# BPMLabRXDriver.net
KiCad netlist of a schematic drawn in EAGLE
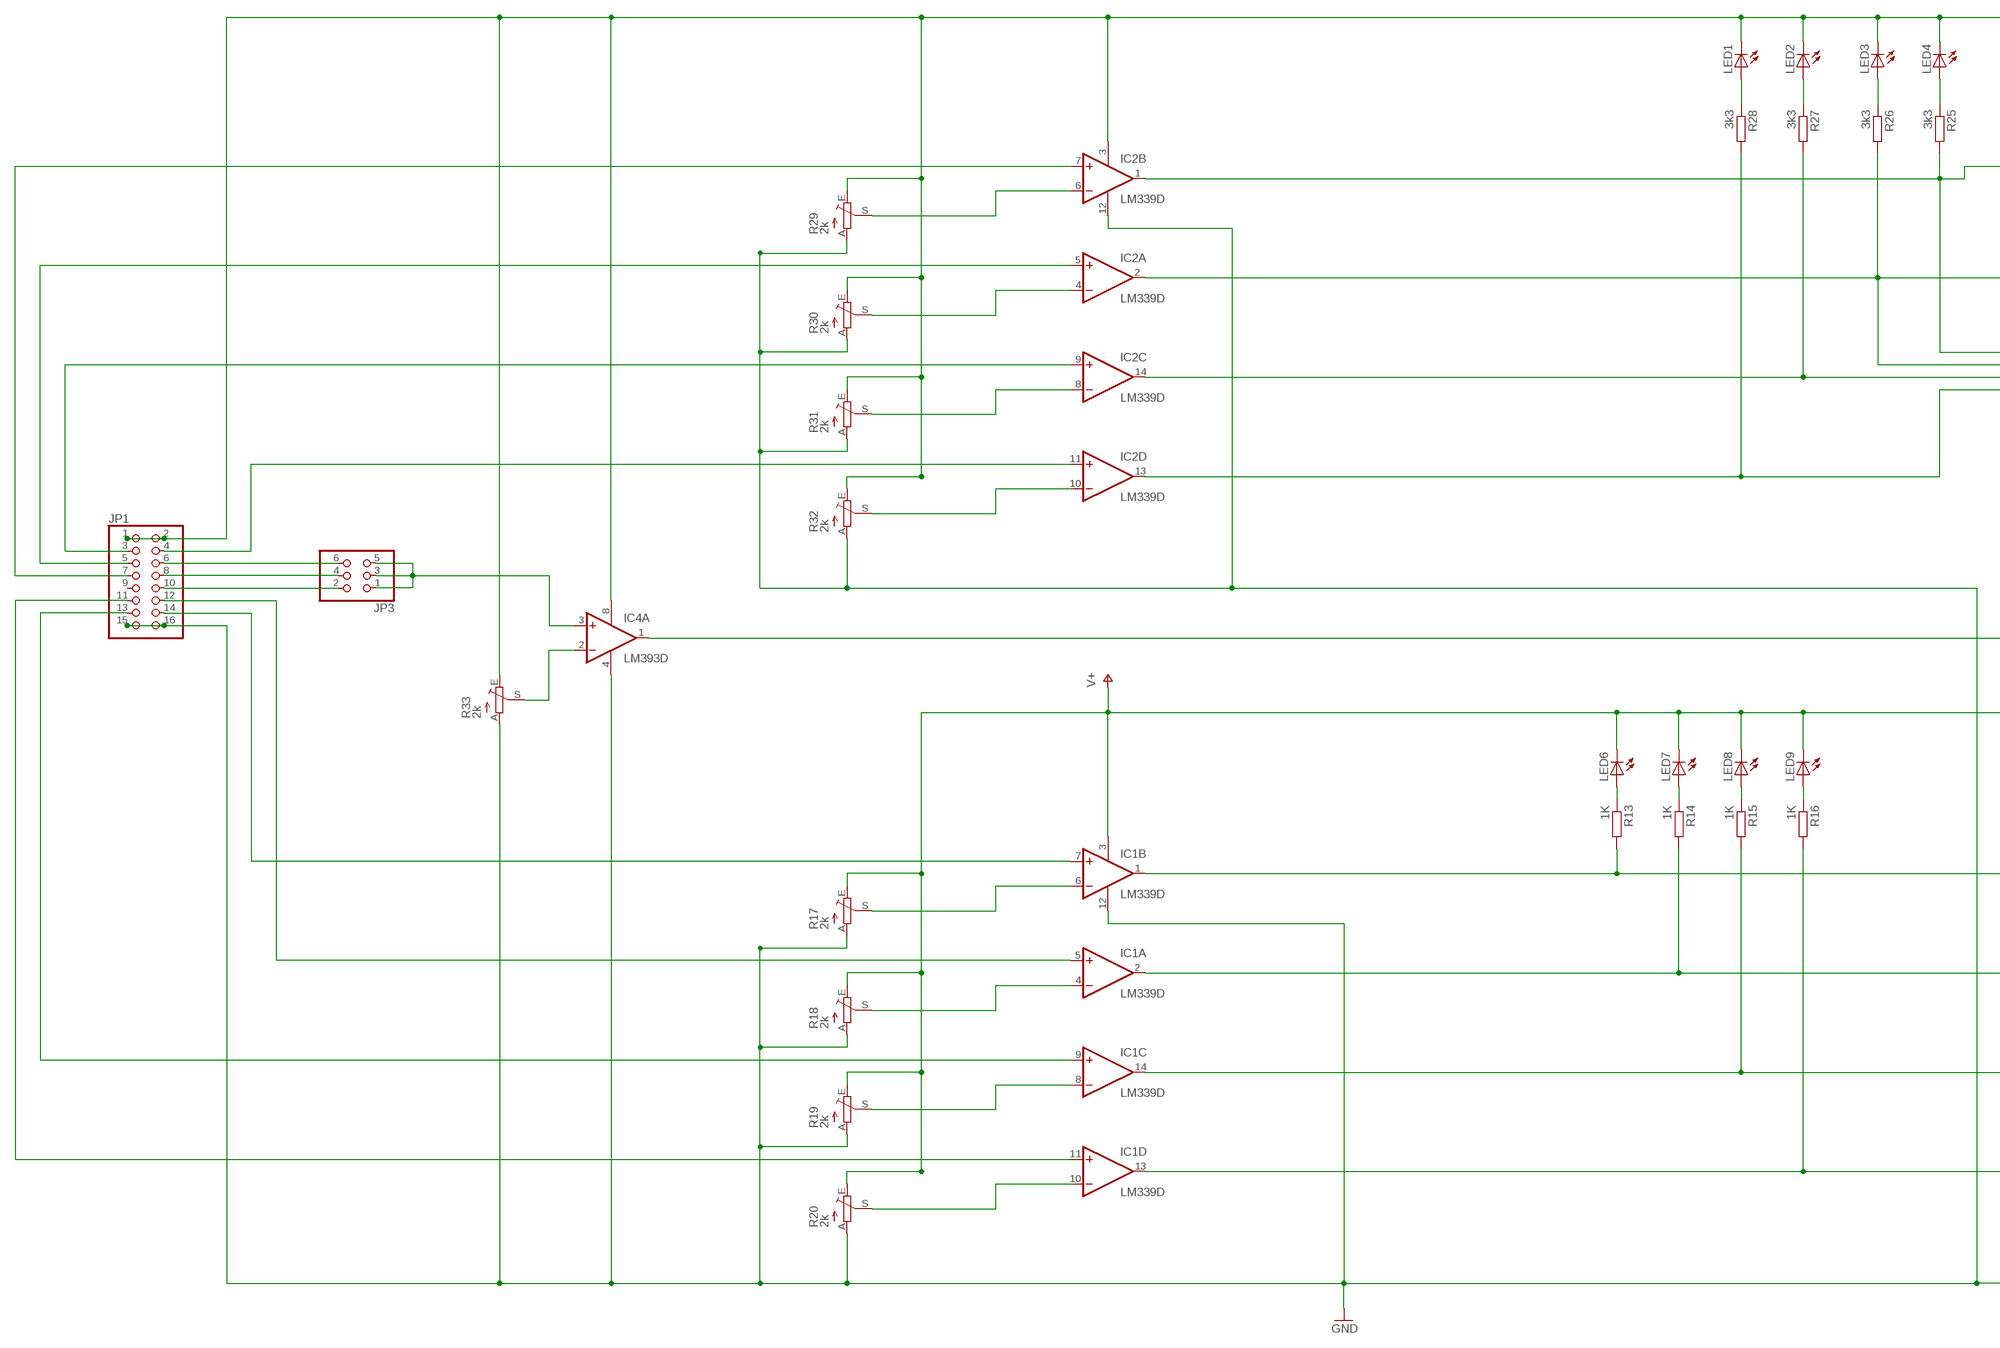
[diagram p0: schematic, sheet 1, part 1 of 2]
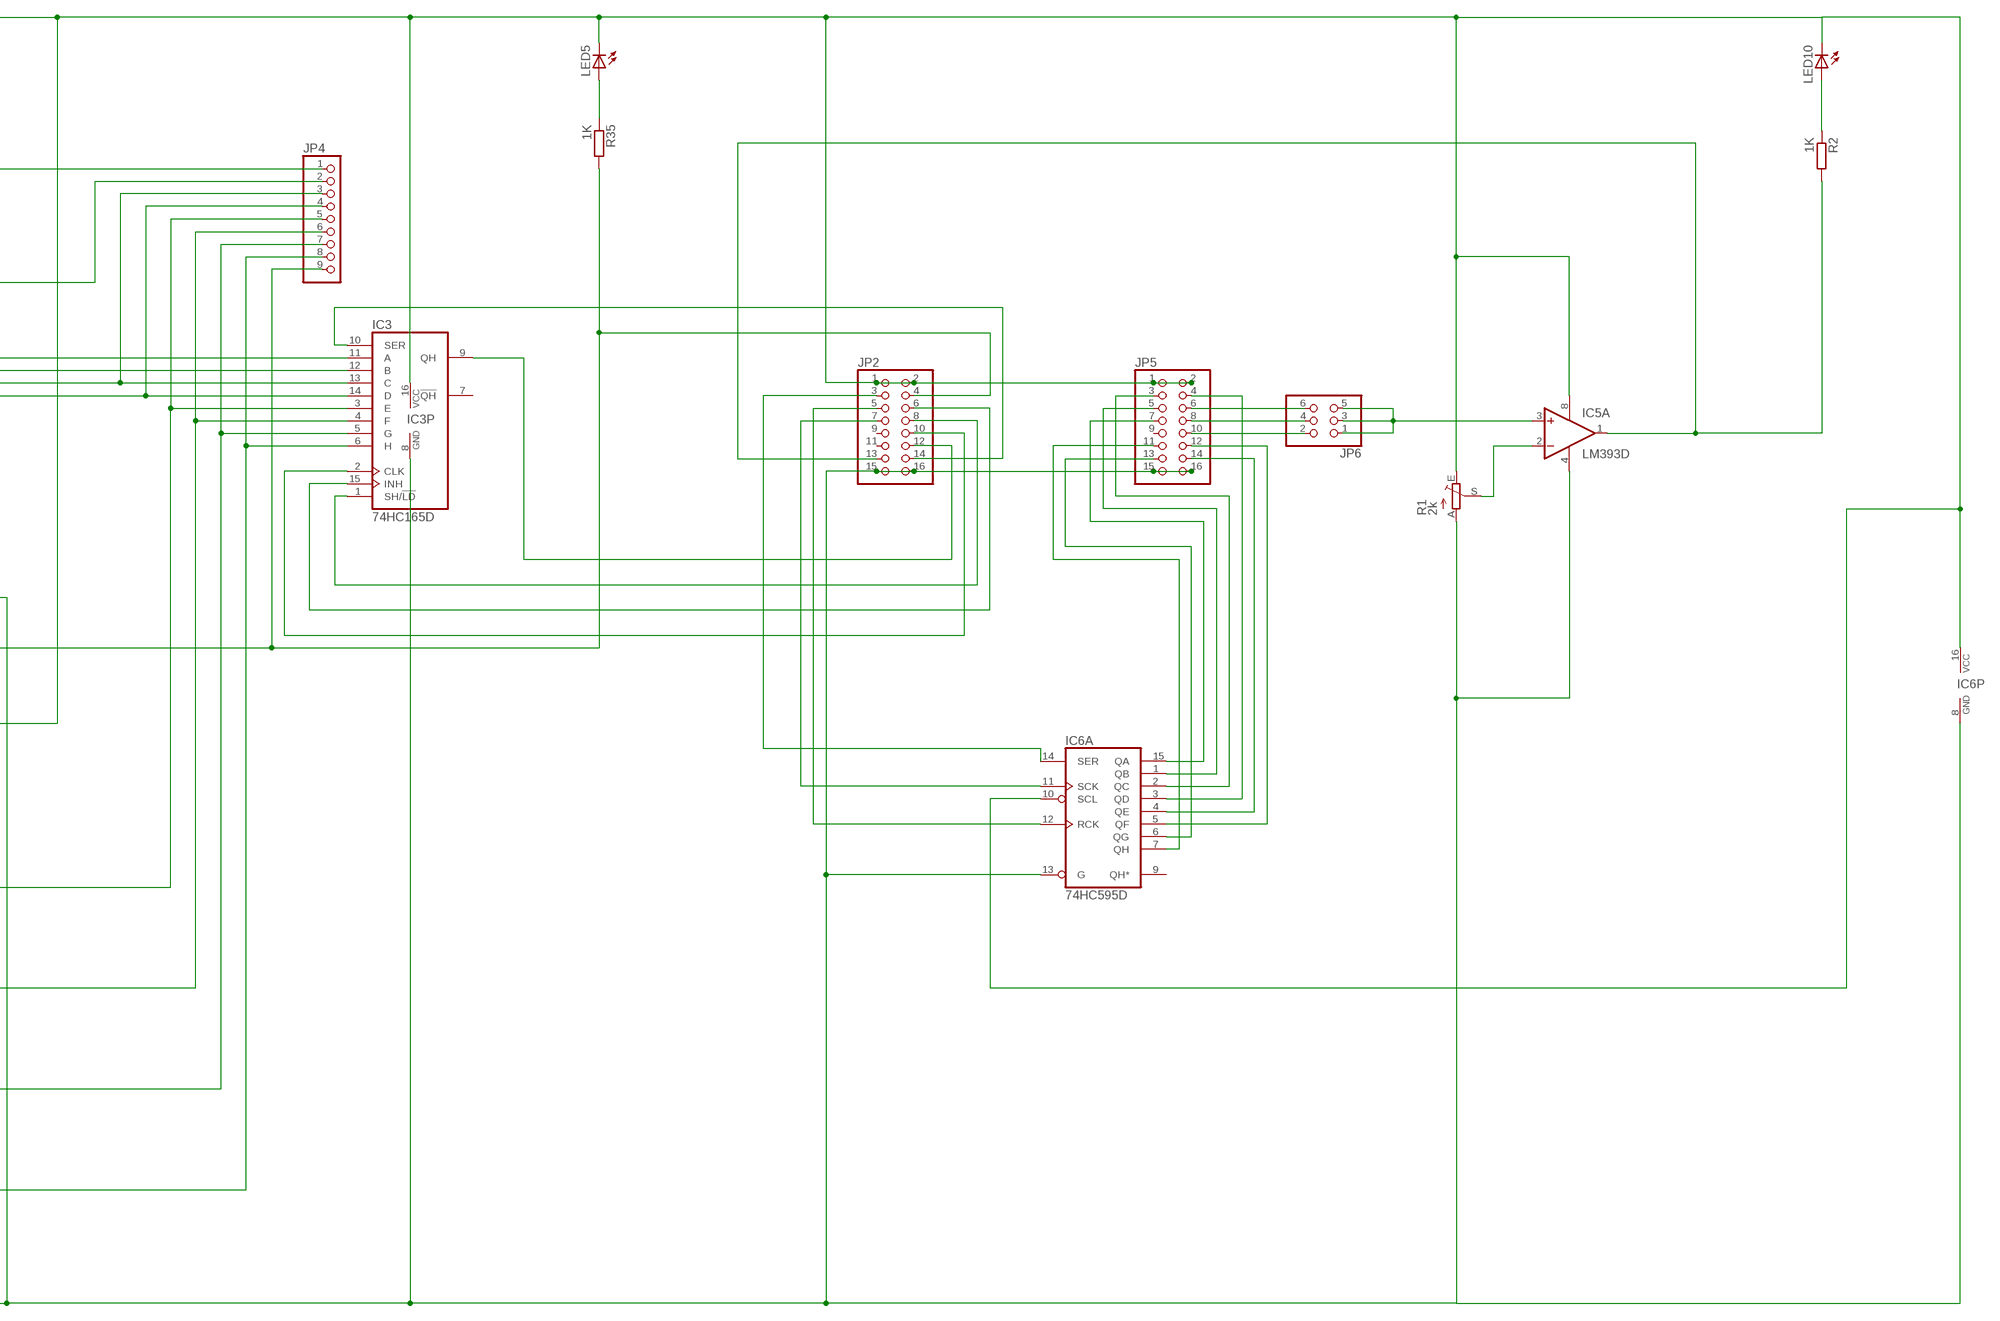
[diagram p1: schematic, sheet 1, part 2 of 2]

(export (version "E")
  (design (tool "Eeschema 10.0.6"))
  (components
    (comp (ref "IC1")
      (value "LM339D")
      (footprint "eagle-import:SO14")
      (libsource (lib "eagle-import") (part "LM339D"))
    )
    (comp (ref "IC2")
      (value "LM339D")
      (footprint "eagle-import:SO14")
      (libsource (lib "eagle-import") (part "LM339D"))
    )
    (comp (ref "IC3")
      (value "74HC165D")
      (footprint "eagle-import:SO16")
      (libsource (lib "eagle-import") (part "74165DHC"))
    )
    (comp (ref "IC4")
      (value "LM393D")
      (footprint "eagle-import:SO08")
      (libsource (lib "eagle-import") (part "LM393D"))
    )
    (comp (ref "IC5")
      (value "LM393D")
      (footprint "eagle-import:SO08")
      (libsource (lib "eagle-import") (part "LM393D"))
    )
    (comp (ref "IC6")
      (value "74HC595D")
      (footprint "eagle-import:SO16")
      (libsource (lib "eagle-import") (part "74595DHC"))
    )
    (comp (ref "JP1")
      (value "PINHD-2X8")
      (footprint "eagle-import:2X08")
      (libsource (lib "eagle-import") (part "PINHD-2X8"))
    )
    (comp (ref "JP2")
      (value "PINHD-2X8")
      (footprint "eagle-import:2X08")
      (libsource (lib "eagle-import") (part "PINHD-2X8"))
    )
    (comp (ref "JP3")
      (value "PINHD-2X3")
      (footprint "eagle-import:2X03")
      (libsource (lib "eagle-import") (part "PINHD-2X3"))
    )
    (comp (ref "JP4")
      (value "PINHD-1X9")
      (footprint "eagle-import:1X09")
      (libsource (lib "eagle-import") (part "PINHD-1X9"))
    )
    (comp (ref "JP5")
      (value "PINHD-2X8")
      (footprint "eagle-import:2X08")
      (libsource (lib "eagle-import") (part "PINHD-2X8"))
    )
    (comp (ref "JP6")
      (value "PINHD-2X3")
      (footprint "eagle-import:2X03")
      (libsource (lib "eagle-import") (part "PINHD-2X3"))
    )
    (comp (ref "LED1")
      (value "LED5MM")
      (footprint "eagle-import:LED5MM")
      (libsource (lib "eagle-import") (part "LED5MM"))
    )
    (comp (ref "LED2")
      (value "LED5MM")
      (footprint "eagle-import:LED5MM")
      (libsource (lib "eagle-import") (part "LED5MM"))
    )
    (comp (ref "LED3")
      (value "LED5MM")
      (footprint "eagle-import:LED5MM")
      (libsource (lib "eagle-import") (part "LED5MM"))
    )
    (comp (ref "LED4")
      (value "LED5MM")
      (footprint "eagle-import:LED5MM")
      (libsource (lib "eagle-import") (part "LED5MM"))
    )
    (comp (ref "LED5")
      (value "LED5MM")
      (footprint "eagle-import:LED5MM")
      (libsource (lib "eagle-import") (part "LED5MM"))
    )
    (comp (ref "LED6")
      (value "LED5MM")
      (footprint "eagle-import:LED5MM")
      (libsource (lib "eagle-import") (part "LED5MM"))
    )
    (comp (ref "LED7")
      (value "LED5MM")
      (footprint "eagle-import:LED5MM")
      (libsource (lib "eagle-import") (part "LED5MM"))
    )
    (comp (ref "LED8")
      (value "LED5MM")
      (footprint "eagle-import:LED5MM")
      (libsource (lib "eagle-import") (part "LED5MM"))
    )
    (comp (ref "LED9")
      (value "LED5MM")
      (footprint "eagle-import:LED5MM")
      (libsource (lib "eagle-import") (part "LED5MM"))
    )
    (comp (ref "LED10")
      (value "LED5MM")
      (footprint "eagle-import:LED5MM")
      (libsource (lib "eagle-import") (part "LED5MM"))
    )
    (comp (ref "R1")
      (value "2k")
      (footprint "eagle-import:RS3")
      (libsource (lib "eagle-import") (part "TRIM_EU-RS3"))
    )
    (comp (ref "R2")
      (value "1K")
      (footprint "eagle-import:M0805")
      (libsource (lib "eagle-import") (part "R-EU_M0805"))
    )
    (comp (ref "R13")
      (value "1K")
      (footprint "eagle-import:M0805")
      (libsource (lib "eagle-import") (part "R-EU_M0805"))
    )
    (comp (ref "R14")
      (value "1K")
      (footprint "eagle-import:M0805")
      (libsource (lib "eagle-import") (part "R-EU_M0805"))
    )
    (comp (ref "R15")
      (value "1K")
      (footprint "eagle-import:M0805")
      (libsource (lib "eagle-import") (part "R-EU_M0805"))
    )
    (comp (ref "R16")
      (value "1K")
      (footprint "eagle-import:M0805")
      (libsource (lib "eagle-import") (part "R-EU_M0805"))
    )
    (comp (ref "R17")
      (value "2k")
      (footprint "eagle-import:RS3")
      (libsource (lib "eagle-import") (part "TRIM_EU-RS3"))
    )
    (comp (ref "R18")
      (value "2k")
      (footprint "eagle-import:RS3")
      (libsource (lib "eagle-import") (part "TRIM_EU-RS3"))
    )
    (comp (ref "R19")
      (value "2k")
      (footprint "eagle-import:RS3")
      (libsource (lib "eagle-import") (part "TRIM_EU-RS3"))
    )
    (comp (ref "R20")
      (value "2k")
      (footprint "eagle-import:RS3")
      (libsource (lib "eagle-import") (part "TRIM_EU-RS3"))
    )
    (comp (ref "R25")
      (value "3k3")
      (footprint "eagle-import:M0805")
      (libsource (lib "eagle-import") (part "R-EU_M0805"))
    )
    (comp (ref "R26")
      (value "3k3")
      (footprint "eagle-import:M0805")
      (libsource (lib "eagle-import") (part "R-EU_M0805"))
    )
    (comp (ref "R27")
      (value "3k3")
      (footprint "eagle-import:M0805")
      (libsource (lib "eagle-import") (part "R-EU_M0805"))
    )
    (comp (ref "R28")
      (value "3k3")
      (footprint "eagle-import:M0805")
      (libsource (lib "eagle-import") (part "R-EU_M0805"))
    )
    (comp (ref "R29")
      (value "2k")
      (footprint "eagle-import:RS3")
      (libsource (lib "eagle-import") (part "TRIM_EU-RS3"))
    )
    (comp (ref "R30")
      (value "2k")
      (footprint "eagle-import:RS3")
      (libsource (lib "eagle-import") (part "TRIM_EU-RS3"))
    )
    (comp (ref "R31")
      (value "2k")
      (footprint "eagle-import:RS3")
      (libsource (lib "eagle-import") (part "TRIM_EU-RS3"))
    )
    (comp (ref "R32")
      (value "2k")
      (footprint "eagle-import:RS3")
      (libsource (lib "eagle-import") (part "TRIM_EU-RS3"))
    )
    (comp (ref "R33")
      (value "2k")
      (footprint "eagle-import:RS3")
      (libsource (lib "eagle-import") (part "TRIM_EU-RS3"))
    )
    (comp (ref "R35")
      (value "1K")
      (footprint "eagle-import:M0805")
      (libsource (lib "eagle-import") (part "R-EU_M0805"))
    )
  )
  (nets
    (net (code "1") (name "GND") (class "Default")
      (node (ref "IC1") (pin "12") (pinfunction "GND_12") (pintype "power_in"))
      (node (ref "IC2") (pin "12") (pinfunction "GND_12") (pintype "power_in"))
      (node (ref "IC3") (pin "8") (pinfunction "GND_8") (pintype "power_in"))
      (node (ref "IC4") (pin "4") (pinfunction "V-_4") (pintype "power_in"))
      (node (ref "IC5") (pin "4") (pinfunction "V-_4") (pintype "power_in"))
      (node (ref "IC6") (pin "13") (pinfunction "G_13") (pintype "input"))
      (node (ref "IC6") (pin "8") (pinfunction "GND_8") (pintype "power_in"))
      (node (ref "JP1") (pin "15") (pinfunction "15_15") (pintype "passive"))
      (node (ref "JP1") (pin "16") (pinfunction "16_16") (pintype "passive"))
      (node (ref "JP2") (pin "15") (pinfunction "15_15") (pintype "passive"))
      (node (ref "JP2") (pin "16") (pinfunction "16_16") (pintype "passive"))
      (node (ref "JP5") (pin "15") (pinfunction "15_15") (pintype "passive"))
      (node (ref "JP5") (pin "16") (pinfunction "16_16") (pintype "passive"))
      (node (ref "R1") (pin "A") (pinfunction "A_A") (pintype "passive"))
      (node (ref "R17") (pin "A") (pinfunction "A_A") (pintype "passive"))
      (node (ref "R18") (pin "A") (pinfunction "A_A") (pintype "passive"))
      (node (ref "R19") (pin "A") (pinfunction "A_A") (pintype "passive"))
      (node (ref "R20") (pin "A") (pinfunction "A_A") (pintype "passive"))
      (node (ref "R29") (pin "A") (pinfunction "A_A") (pintype "passive"))
      (node (ref "R30") (pin "A") (pinfunction "A_A") (pintype "passive"))
      (node (ref "R31") (pin "A") (pinfunction "A_A") (pintype "passive"))
      (node (ref "R32") (pin "A") (pinfunction "A_A") (pintype "passive"))
      (node (ref "R33") (pin "A") (pinfunction "A_A") (pintype "passive"))
    )
    (net (code "2") (name "Net-(IC1A-+IN)") (class "Default")
      (node (ref "IC1") (pin "5") (pinfunction "+IN_5") (pintype "input"))
      (node (ref "JP1") (pin "12") (pinfunction "12_12") (pintype "passive"))
    )
    (net (code "3") (name "Net-(IC1A--IN)") (class "Default")
      (node (ref "IC1") (pin "4") (pinfunction "-IN_4") (pintype "input"))
      (node (ref "R18") (pin "S") (pinfunction "S_S") (pintype "passive"))
    )
    (net (code "4") (name "Net-(IC1A-OUT)") (class "Default")
      (node (ref "IC1") (pin "2") (pinfunction "OUT_2") (pintype "open_collector"))
      (node (ref "IC3") (pin "4") (pinfunction "F_4") (pintype "input"))
      (node (ref "JP4") (pin "6") (pinfunction "6_6") (pintype "passive"))
      (node (ref "R14") (pin "2") (pinfunction "2_2") (pintype "passive"))
    )
    (net (code "5") (name "Net-(IC1B-+IN)") (class "Default")
      (node (ref "IC1") (pin "7") (pinfunction "+IN_7") (pintype "input"))
      (node (ref "JP1") (pin "14") (pinfunction "14_14") (pintype "passive"))
    )
    (net (code "6") (name "Net-(IC1B--IN)") (class "Default")
      (node (ref "IC1") (pin "6") (pinfunction "-IN_6") (pintype "input"))
      (node (ref "R17") (pin "S") (pinfunction "S_S") (pintype "passive"))
    )
    (net (code "7") (name "Net-(IC1B-OUT)") (class "Default")
      (node (ref "IC1") (pin "1") (pinfunction "OUT_1") (pintype "open_collector"))
      (node (ref "IC3") (pin "3") (pinfunction "E_3") (pintype "input"))
      (node (ref "JP4") (pin "5") (pinfunction "5_5") (pintype "passive"))
      (node (ref "R13") (pin "2") (pinfunction "2_2") (pintype "passive"))
    )
    (net (code "8") (name "Net-(IC1C-+IN)") (class "Default")
      (node (ref "IC1") (pin "9") (pinfunction "+IN_9") (pintype "input"))
      (node (ref "JP1") (pin "13") (pinfunction "13_13") (pintype "passive"))
    )
    (net (code "9") (name "Net-(IC1C--IN)") (class "Default")
      (node (ref "IC1") (pin "8") (pinfunction "-IN_8") (pintype "input"))
      (node (ref "R19") (pin "S") (pinfunction "S_S") (pintype "passive"))
    )
    (net (code "10") (name "Net-(IC1C-OUT)") (class "Default")
      (node (ref "IC1") (pin "14") (pinfunction "OUT_14") (pintype "open_collector"))
      (node (ref "IC3") (pin "5") (pinfunction "G_5") (pintype "input"))
      (node (ref "JP4") (pin "7") (pinfunction "7_7") (pintype "passive"))
      (node (ref "R15") (pin "2") (pinfunction "2_2") (pintype "passive"))
    )
    (net (code "11") (name "Net-(IC1D-+IN)") (class "Default")
      (node (ref "IC1") (pin "11") (pinfunction "+IN_11") (pintype "input"))
      (node (ref "JP1") (pin "11") (pinfunction "11_11") (pintype "passive"))
    )
    (net (code "12") (name "Net-(IC1D--IN)") (class "Default")
      (node (ref "IC1") (pin "10") (pinfunction "-IN_10") (pintype "input"))
      (node (ref "R20") (pin "S") (pinfunction "S_S") (pintype "passive"))
    )
    (net (code "13") (name "Net-(IC1D-OUT)") (class "Default")
      (node (ref "IC1") (pin "13") (pinfunction "OUT_13") (pintype "open_collector"))
      (node (ref "IC3") (pin "6") (pinfunction "H_6") (pintype "input"))
      (node (ref "JP4") (pin "8") (pinfunction "8_8") (pintype "passive"))
      (node (ref "R16") (pin "2") (pinfunction "2_2") (pintype "passive"))
    )
    (net (code "14") (name "Net-(IC2A-+IN)") (class "Default")
      (node (ref "IC2") (pin "5") (pinfunction "+IN_5") (pintype "input"))
      (node (ref "JP1") (pin "5") (pinfunction "5_5") (pintype "passive"))
    )
    (net (code "15") (name "Net-(IC2A--IN)") (class "Default")
      (node (ref "IC2") (pin "4") (pinfunction "-IN_4") (pintype "input"))
      (node (ref "R30") (pin "S") (pinfunction "S_S") (pintype "passive"))
    )
    (net (code "16") (name "Net-(IC2A-OUT)") (class "Default")
      (node (ref "IC2") (pin "2") (pinfunction "OUT_2") (pintype "open_collector"))
      (node (ref "IC3") (pin "12") (pinfunction "B_12") (pintype "input"))
      (node (ref "JP4") (pin "2") (pinfunction "2_2") (pintype "passive"))
      (node (ref "R26") (pin "2") (pinfunction "2_2") (pintype "passive"))
    )
    (net (code "17") (name "Net-(IC2B-+IN)") (class "Default")
      (node (ref "IC2") (pin "7") (pinfunction "+IN_7") (pintype "input"))
      (node (ref "JP1") (pin "7") (pinfunction "7_7") (pintype "passive"))
    )
    (net (code "18") (name "Net-(IC2B--IN)") (class "Default")
      (node (ref "IC2") (pin "6") (pinfunction "-IN_6") (pintype "input"))
      (node (ref "R29") (pin "S") (pinfunction "S_S") (pintype "passive"))
    )
    (net (code "19") (name "Net-(IC2B-OUT)") (class "Default")
      (node (ref "IC2") (pin "1") (pinfunction "OUT_1") (pintype "open_collector"))
      (node (ref "IC3") (pin "11") (pinfunction "A_11") (pintype "input"))
      (node (ref "JP4") (pin "1") (pinfunction "1_1") (pintype "passive"))
      (node (ref "R25") (pin "2") (pinfunction "2_2") (pintype "passive"))
    )
    (net (code "20") (name "Net-(IC2C-+IN)") (class "Default")
      (node (ref "IC2") (pin "9") (pinfunction "+IN_9") (pintype "input"))
      (node (ref "JP1") (pin "3") (pinfunction "3_3") (pintype "passive"))
    )
    (net (code "21") (name "Net-(IC2C--IN)") (class "Default")
      (node (ref "IC2") (pin "8") (pinfunction "-IN_8") (pintype "input"))
      (node (ref "R31") (pin "S") (pinfunction "S_S") (pintype "passive"))
    )
    (net (code "22") (name "Net-(IC2C-OUT)") (class "Default")
      (node (ref "IC2") (pin "14") (pinfunction "OUT_14") (pintype "open_collector"))
      (node (ref "IC3") (pin "13") (pinfunction "C_13") (pintype "input"))
      (node (ref "JP4") (pin "3") (pinfunction "3_3") (pintype "passive"))
      (node (ref "R27") (pin "2") (pinfunction "2_2") (pintype "passive"))
    )
    (net (code "23") (name "Net-(IC2D-+IN)") (class "Default")
      (node (ref "IC2") (pin "11") (pinfunction "+IN_11") (pintype "input"))
      (node (ref "JP1") (pin "4") (pinfunction "4_4") (pintype "passive"))
    )
    (net (code "24") (name "Net-(IC2D--IN)") (class "Default")
      (node (ref "IC2") (pin "10") (pinfunction "-IN_10") (pintype "input"))
      (node (ref "R32") (pin "S") (pinfunction "S_S") (pintype "passive"))
    )
    (net (code "25") (name "Net-(IC2D-OUT)") (class "Default")
      (node (ref "IC2") (pin "13") (pinfunction "OUT_13") (pintype "open_collector"))
      (node (ref "IC3") (pin "14") (pinfunction "D_14") (pintype "input"))
      (node (ref "JP4") (pin "4") (pinfunction "4_4") (pintype "passive"))
      (node (ref "R28") (pin "2") (pinfunction "2_2") (pintype "passive"))
    )
    (net (code "26") (name "Net-(IC3A-CLK)") (class "Default")
      (node (ref "IC3") (pin "2") (pinfunction "CLK_2") (pintype "input"))
      (node (ref "JP2") (pin "10") (pinfunction "10_10") (pintype "passive"))
    )
    (net (code "27") (name "Net-(IC3A-INH)") (class "Default")
      (node (ref "IC3") (pin "15") (pinfunction "INH_15") (pintype "input"))
      (node (ref "JP2") (pin "6") (pinfunction "6_6") (pintype "passive"))
    )
    (net (code "28") (name "Net-(IC3A-QH)") (class "Default")
      (node (ref "IC3") (pin "9") (pinfunction "QH_9") (pintype "output"))
      (node (ref "JP2") (pin "12") (pinfunction "12_12") (pintype "passive"))
    )
    (net (code "29") (name "Net-(IC3A-SER)") (class "Default")
      (node (ref "IC3") (pin "10") (pinfunction "SER_10") (pintype "input"))
      (node (ref "JP2") (pin "14") (pinfunction "14_14") (pintype "passive"))
    )
    (net (code "30") (name "Net-(IC3A-SH{slash}~{LD})") (class "Default")
      (node (ref "IC3") (pin "1") (pinfunction "SH/~{LD}_1") (pintype "input"))
      (node (ref "JP2") (pin "8") (pinfunction "8_8") (pintype "passive"))
    )
    (net (code "31") (name "Net-(IC4A-+IN)") (class "Default")
      (node (ref "IC4") (pin "3") (pinfunction "+IN_3") (pintype "input"))
      (node (ref "JP3") (pin "1") (pinfunction "1_1") (pintype "passive"))
      (node (ref "JP3") (pin "3") (pinfunction "3_3") (pintype "passive"))
      (node (ref "JP3") (pin "5") (pinfunction "5_5") (pintype "passive"))
    )
    (net (code "32") (name "Net-(IC4A--IN)") (class "Default")
      (node (ref "IC4") (pin "2") (pinfunction "-IN_2") (pintype "input"))
      (node (ref "R33") (pin "S") (pinfunction "S_S") (pintype "passive"))
    )
    (net (code "33") (name "Net-(IC4A-OUT)") (class "Default")
      (node (ref "IC4") (pin "1") (pinfunction "OUT_1") (pintype "output"))
      (node (ref "JP2") (pin "4") (pinfunction "4_4") (pintype "passive"))
      (node (ref "JP4") (pin "9") (pinfunction "9_9") (pintype "passive"))
      (node (ref "R35") (pin "2") (pinfunction "2_2") (pintype "passive"))
    )
    (net (code "34") (name "Net-(IC5A-+IN)") (class "Default")
      (node (ref "IC5") (pin "3") (pinfunction "+IN_3") (pintype "input"))
      (node (ref "JP6") (pin "1") (pinfunction "1_1") (pintype "passive"))
      (node (ref "JP6") (pin "3") (pinfunction "3_3") (pintype "passive"))
      (node (ref "JP6") (pin "5") (pinfunction "5_5") (pintype "passive"))
    )
    (net (code "35") (name "Net-(IC5A--IN)") (class "Default")
      (node (ref "IC5") (pin "2") (pinfunction "-IN_2") (pintype "input"))
      (node (ref "R1") (pin "S") (pinfunction "S_S") (pintype "passive"))
    )
    (net (code "36") (name "Net-(IC5A-OUT)") (class "Default")
      (node (ref "IC5") (pin "1") (pinfunction "OUT_1") (pintype "output"))
      (node (ref "JP2") (pin "13") (pinfunction "13_13") (pintype "passive"))
      (node (ref "R2") (pin "2") (pinfunction "2_2") (pintype "passive"))
    )
    (net (code "37") (name "Net-(IC6A-QA)") (class "Default")
      (node (ref "IC6") (pin "15") (pinfunction "QA_15") (pintype "tri_state"))
      (node (ref "JP5") (pin "7") (pinfunction "7_7") (pintype "passive"))
    )
    (net (code "38") (name "Net-(IC6A-QB)") (class "Default")
      (node (ref "IC6") (pin "1") (pinfunction "QB_1") (pintype "tri_state"))
      (node (ref "JP5") (pin "5") (pinfunction "5_5") (pintype "passive"))
    )
    (net (code "39") (name "Net-(IC6A-QC)") (class "Default")
      (node (ref "IC6") (pin "2") (pinfunction "QC_2") (pintype "tri_state"))
      (node (ref "JP5") (pin "3") (pinfunction "3_3") (pintype "passive"))
    )
    (net (code "40") (name "Net-(IC6A-QD)") (class "Default")
      (node (ref "IC6") (pin "3") (pinfunction "QD_3") (pintype "tri_state"))
      (node (ref "JP5") (pin "4") (pinfunction "4_4") (pintype "passive"))
    )
    (net (code "41") (name "Net-(IC6A-QE)") (class "Default")
      (node (ref "IC6") (pin "4") (pinfunction "QE_4") (pintype "tri_state"))
      (node (ref "JP5") (pin "14") (pinfunction "14_14") (pintype "passive"))
    )
    (net (code "42") (name "Net-(IC6A-QF)") (class "Default")
      (node (ref "IC6") (pin "5") (pinfunction "QF_5") (pintype "tri_state"))
      (node (ref "JP5") (pin "12") (pinfunction "12_12") (pintype "passive"))
    )
    (net (code "43") (name "Net-(IC6A-QG)") (class "Default")
      (node (ref "IC6") (pin "6") (pinfunction "QG_6") (pintype "tri_state"))
      (node (ref "JP5") (pin "13") (pinfunction "13_13") (pintype "passive"))
    )
    (net (code "44") (name "Net-(IC6A-QH)") (class "Default")
      (node (ref "IC6") (pin "7") (pinfunction "QH_7") (pintype "tri_state"))
      (node (ref "JP5") (pin "11") (pinfunction "11_11") (pintype "passive"))
    )
    (net (code "45") (name "Net-(IC6A-RCK)") (class "Default")
      (node (ref "IC6") (pin "12") (pinfunction "RCK_12") (pintype "input"))
      (node (ref "JP2") (pin "5") (pinfunction "5_5") (pintype "passive"))
    )
    (net (code "46") (name "Net-(IC6A-SCK)") (class "Default")
      (node (ref "IC6") (pin "11") (pinfunction "SCK_11") (pintype "input"))
      (node (ref "JP2") (pin "7") (pinfunction "7_7") (pintype "passive"))
    )
    (net (code "47") (name "Net-(IC6A-SER)") (class "Default")
      (node (ref "IC6") (pin "14") (pinfunction "SER_14") (pintype "input"))
      (node (ref "JP2") (pin "3") (pinfunction "3_3") (pintype "passive"))
    )
    (net (code "48") (name "Net-(JP1-Pad6)") (class "Default")
      (node (ref "JP1") (pin "6") (pinfunction "6_6") (pintype "passive"))
      (node (ref "JP3") (pin "6") (pinfunction "6_6") (pintype "passive"))
    )
    (net (code "49") (name "Net-(JP1-Pad8)") (class "Default")
      (node (ref "JP1") (pin "8") (pinfunction "8_8") (pintype "passive"))
      (node (ref "JP3") (pin "4") (pinfunction "4_4") (pintype "passive"))
    )
    (net (code "50") (name "Net-(JP1-Pad10)") (class "Default")
      (node (ref "JP1") (pin "10") (pinfunction "10_10") (pintype "passive"))
      (node (ref "JP3") (pin "2") (pinfunction "2_2") (pintype "passive"))
    )
    (net (code "51") (name "Net-(JP5-Pad6)") (class "Default")
      (node (ref "JP5") (pin "6") (pinfunction "6_6") (pintype "passive"))
      (node (ref "JP6") (pin "6") (pinfunction "6_6") (pintype "passive"))
    )
    (net (code "52") (name "Net-(JP5-Pad8)") (class "Default")
      (node (ref "JP5") (pin "8") (pinfunction "8_8") (pintype "passive"))
      (node (ref "JP6") (pin "4") (pinfunction "4_4") (pintype "passive"))
    )
    (net (code "53") (name "Net-(JP5-Pad10)") (class "Default")
      (node (ref "JP5") (pin "10") (pinfunction "10_10") (pintype "passive"))
      (node (ref "JP6") (pin "2") (pinfunction "2_2") (pintype "passive"))
    )
    (net (code "54") (name "Net-(LED1-PadA)") (class "Default")
      (node (ref "LED1") (pin "A") (pinfunction "A_A") (pintype "passive"))
      (node (ref "R28") (pin "1") (pinfunction "1_1") (pintype "passive"))
    )
    (net (code "55") (name "Net-(LED2-PadA)") (class "Default")
      (node (ref "LED2") (pin "A") (pinfunction "A_A") (pintype "passive"))
      (node (ref "R27") (pin "1") (pinfunction "1_1") (pintype "passive"))
    )
    (net (code "56") (name "Net-(LED3-PadA)") (class "Default")
      (node (ref "LED3") (pin "A") (pinfunction "A_A") (pintype "passive"))
      (node (ref "R26") (pin "1") (pinfunction "1_1") (pintype "passive"))
    )
    (net (code "57") (name "Net-(LED4-PadA)") (class "Default")
      (node (ref "LED4") (pin "A") (pinfunction "A_A") (pintype "passive"))
      (node (ref "R25") (pin "1") (pinfunction "1_1") (pintype "passive"))
    )
    (net (code "58") (name "Net-(LED5-PadA)") (class "Default")
      (node (ref "LED5") (pin "A") (pinfunction "A_A") (pintype "passive"))
      (node (ref "R35") (pin "1") (pinfunction "1_1") (pintype "passive"))
    )
    (net (code "59") (name "Net-(LED6-PadA)") (class "Default")
      (node (ref "LED6") (pin "A") (pinfunction "A_A") (pintype "passive"))
      (node (ref "R13") (pin "1") (pinfunction "1_1") (pintype "passive"))
    )
    (net (code "60") (name "Net-(LED7-PadA)") (class "Default")
      (node (ref "LED7") (pin "A") (pinfunction "A_A") (pintype "passive"))
      (node (ref "R14") (pin "1") (pinfunction "1_1") (pintype "passive"))
    )
    (net (code "61") (name "Net-(LED8-PadA)") (class "Default")
      (node (ref "LED8") (pin "A") (pinfunction "A_A") (pintype "passive"))
      (node (ref "R15") (pin "1") (pinfunction "1_1") (pintype "passive"))
    )
    (net (code "62") (name "Net-(LED9-PadA)") (class "Default")
      (node (ref "LED9") (pin "A") (pinfunction "A_A") (pintype "passive"))
      (node (ref "R16") (pin "1") (pinfunction "1_1") (pintype "passive"))
    )
    (net (code "63") (name "Net-(LED10-PadA)") (class "Default")
      (node (ref "LED10") (pin "A") (pinfunction "A_A") (pintype "passive"))
      (node (ref "R2") (pin "1") (pinfunction "1_1") (pintype "passive"))
    )
    (net (code "64") (name "V+") (class "Default")
      (node (ref "IC1") (pin "3") (pinfunction "V+_3") (pintype "power_in"))
      (node (ref "IC2") (pin "3") (pinfunction "V+_3") (pintype "power_in"))
      (node (ref "IC3") (pin "16") (pinfunction "VCC_16") (pintype "power_in"))
      (node (ref "IC4") (pin "8") (pinfunction "V+_8") (pintype "power_in"))
      (node (ref "IC5") (pin "8") (pinfunction "V+_8") (pintype "power_in"))
      (node (ref "IC6") (pin "10") (pinfunction "SCL_10") (pintype "input"))
      (node (ref "IC6") (pin "16") (pinfunction "VCC_16") (pintype "power_in"))
      (node (ref "JP1") (pin "1") (pinfunction "1_1") (pintype "passive"))
      (node (ref "JP1") (pin "2") (pinfunction "2_2") (pintype "passive"))
      (node (ref "JP2") (pin "1") (pinfunction "1_1") (pintype "passive"))
      (node (ref "JP2") (pin "2") (pinfunction "2_2") (pintype "passive"))
      (node (ref "JP5") (pin "1") (pinfunction "1_1") (pintype "passive"))
      (node (ref "JP5") (pin "2") (pinfunction "2_2") (pintype "passive"))
      (node (ref "LED1") (pin "K") (pinfunction "C_K") (pintype "passive"))
      (node (ref "LED10") (pin "K") (pinfunction "C_K") (pintype "passive"))
      (node (ref "LED2") (pin "K") (pinfunction "C_K") (pintype "passive"))
      (node (ref "LED3") (pin "K") (pinfunction "C_K") (pintype "passive"))
      (node (ref "LED4") (pin "K") (pinfunction "C_K") (pintype "passive"))
      (node (ref "LED5") (pin "K") (pinfunction "C_K") (pintype "passive"))
      (node (ref "LED6") (pin "K") (pinfunction "C_K") (pintype "passive"))
      (node (ref "LED7") (pin "K") (pinfunction "C_K") (pintype "passive"))
      (node (ref "LED8") (pin "K") (pinfunction "C_K") (pintype "passive"))
      (node (ref "LED9") (pin "K") (pinfunction "C_K") (pintype "passive"))
      (node (ref "R1") (pin "E") (pinfunction "E_E") (pintype "passive"))
      (node (ref "R17") (pin "E") (pinfunction "E_E") (pintype "passive"))
      (node (ref "R18") (pin "E") (pinfunction "E_E") (pintype "passive"))
      (node (ref "R19") (pin "E") (pinfunction "E_E") (pintype "passive"))
      (node (ref "R20") (pin "E") (pinfunction "E_E") (pintype "passive"))
      (node (ref "R29") (pin "E") (pinfunction "E_E") (pintype "passive"))
      (node (ref "R30") (pin "E") (pinfunction "E_E") (pintype "passive"))
      (node (ref "R31") (pin "E") (pinfunction "E_E") (pintype "passive"))
      (node (ref "R32") (pin "E") (pinfunction "E_E") (pintype "passive"))
      (node (ref "R33") (pin "E") (pinfunction "E_E") (pintype "passive"))
    )
    (net (code "65") (name "unconnected-(IC3A-~{QH}-Pad7)") (class "Default")
      (node (ref "IC3") (pin "7") (pinfunction "~{QH}_7") (pintype "output"))
    )
    (net (code "66") (name "unconnected-(IC6A-QH*-Pad9)") (class "Default")
      (node (ref "IC6") (pin "9") (pinfunction "QH*_9") (pintype "tri_state"))
    )
    (net (code "67") (name "unconnected-(JP1-Pad9)") (class "Default")
      (node (ref "JP1") (pin "9") (pinfunction "9_9") (pintype "passive"))
    )
    (net (code "68") (name "unconnected-(JP2-Pad9)") (class "Default")
      (node (ref "JP2") (pin "9") (pinfunction "9_9") (pintype "passive"))
    )
    (net (code "69") (name "unconnected-(JP2-Pad11)") (class "Default")
      (node (ref "JP2") (pin "11") (pinfunction "11_11") (pintype "passive"))
    )
    (net (code "70") (name "unconnected-(JP5-Pad9)") (class "Default")
      (node (ref "JP5") (pin "9") (pinfunction "9_9") (pintype "passive"))
    )
  )
)
